# MultiSensorModul_v4.net
KiCad netlist of a schematic drawn in EAGLE
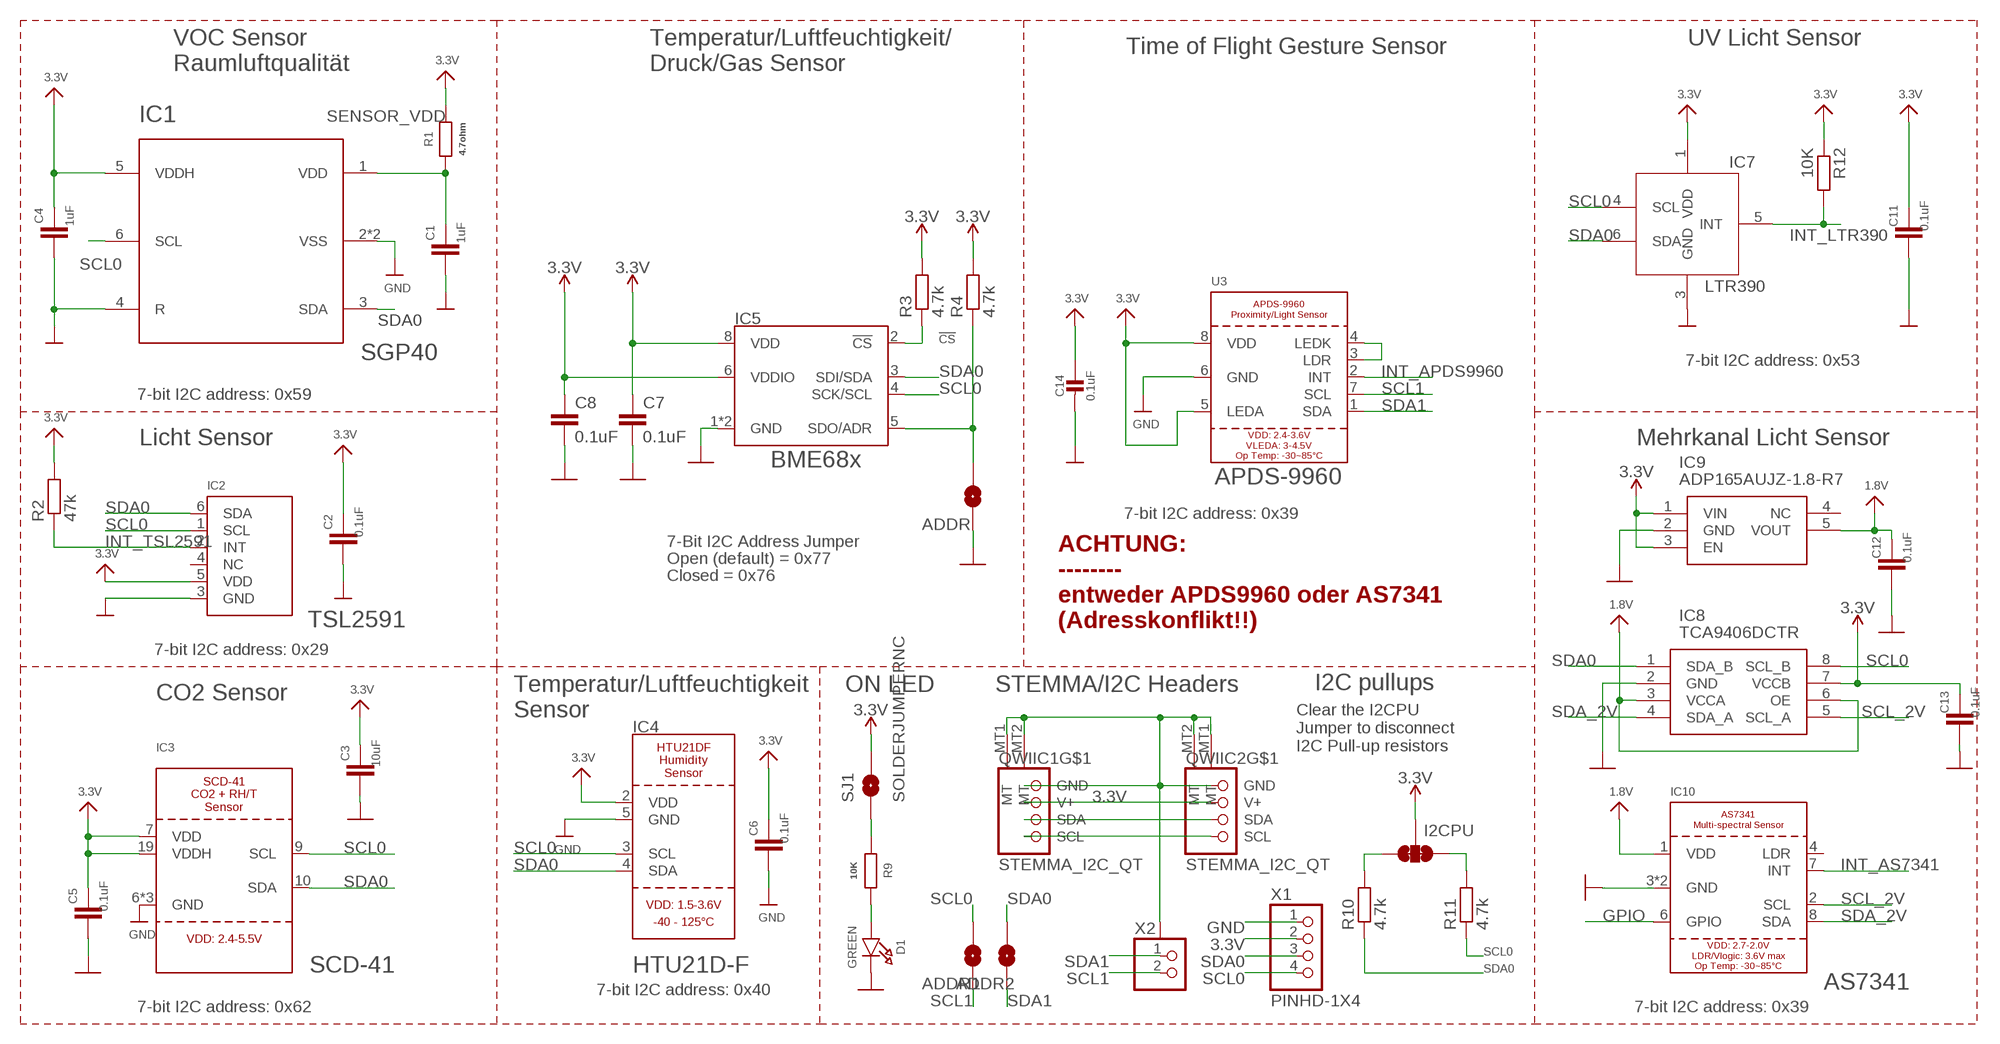
[diagram p0: schematic, sheet 1]

(export (version "E")
  (design (tool "Eeschema 10.0.6"))
  (components
    (comp (ref "ADDR")
      (value "JUMPER-SMT_2_NO_SILK")
      (footprint "eagle-import:SMT-JUMPER_2_NO_SILK")
      (libsource (lib "eagle-import") (part "JUMPER-SMT_2_NO_SILK"))
    )
    (comp (ref "ADDR1")
      (value "JUMPER-SMT_2_NO_SILK")
      (footprint "eagle-import:SMT-JUMPER_2_NO_SILK")
      (libsource (lib "eagle-import") (part "JUMPER-SMT_2_NO_SILK"))
    )
    (comp (ref "ADDR2")
      (value "JUMPER-SMT_2_NO_SILK")
      (footprint "eagle-import:SMT-JUMPER_2_NO_SILK")
      (libsource (lib "eagle-import") (part "JUMPER-SMT_2_NO_SILK"))
    )
    (comp (ref "C1")
      (value "1uF")
      (footprint "eagle-import:C0805")
      (libsource (lib "eagle-import") (part "C-EUC0805"))
    )
    (comp (ref "C2")
      (value "0.1uF")
      (footprint "eagle-import:C0603")
      (libsource (lib "eagle-import") (part "C-EUC0603"))
    )
    (comp (ref "C3")
      (value "10uF")
      (footprint "eagle-import:C0805")
      (libsource (lib "eagle-import") (part "C-EUC0805"))
    )
    (comp (ref "C4")
      (value "1uF")
      (footprint "eagle-import:C0805")
      (libsource (lib "eagle-import") (part "C-EUC0805"))
    )
    (comp (ref "C5")
      (value "0.1uF")
      (footprint "eagle-import:C0603")
      (libsource (lib "eagle-import") (part "C-EUC0603"))
    )
    (comp (ref "C6")
      (value "0.1uF")
      (footprint "eagle-import:C0603")
      (libsource (lib "eagle-import") (part "C-EUC0603"))
    )
    (comp (ref "C7")
      (value "0.1uF")
      (footprint "eagle-import:C0603")
      (libsource (lib "eagle-import") (part "C-EUC0603"))
    )
    (comp (ref "C8")
      (value "0.1uF")
      (footprint "eagle-import:C0603")
      (libsource (lib "eagle-import") (part "C-EUC0603"))
    )
    (comp (ref "C11")
      (value "0.1uF")
      (footprint "eagle-import:C0603")
      (libsource (lib "eagle-import") (part "C-EUC0603"))
    )
    (comp (ref "C12")
      (value "0.1uF")
      (footprint "eagle-import:C0603")
      (libsource (lib "eagle-import") (part "C-EUC0603"))
    )
    (comp (ref "C13")
      (value "0.1uF")
      (footprint "eagle-import:C0603")
      (libsource (lib "eagle-import") (part "C-EUC0603"))
    )
    (comp (ref "C14")
      (value "0.1uF")
      (footprint "eagle-import:0603-NO")
      (libsource (lib "eagle-import") (part "CAP_CERAMIC0603_NO"))
    )
    (comp (ref "D1")
      (value "GREEN")
      (footprint "eagle-import:CHIPLED_0603_NOOUTLINE")
      (libsource (lib "eagle-import") (part "LED0603_NOOUTLINE"))
    )
    (comp (ref "I2CPU")
      (value "I2C PU")
      (footprint "eagle-import:SMT-JUMPER_3_2-NC_TRACE_SILK")
      (libsource (lib "eagle-import") (part "JUMPER-SMT_3_2-NC_TRACE_SILK"))
    )
    (comp (ref "IC1")
      (value "SGP40")
      (footprint "eagle-import:SGP30")
      (libsource (lib "eagle-import") (part "SGP30"))
    )
    (comp (ref "IC2")
      (value "TSL2591")
      (footprint "eagle-import:DFN6_TAOS")
      (libsource (lib "eagle-import") (part "LIGHT_TSL2591"))
    )
    (comp (ref "IC3")
      (value "SCD-41")
      (footprint "eagle-import:SCD41")
      (libsource (lib "eagle-import") (part "SCD-41"))
    )
    (comp (ref "IC4")
      (value "HTU21D-F")
      (footprint "eagle-import:HTU21DF")
      (libsource (lib "eagle-import") (part "HTU21DF"))
    )
    (comp (ref "IC5")
      (value "BME680 Air Quality Sensor")
      (footprint "eagle-import:LGA3.0X3.0")
      (libsource (lib "eagle-import") (part "BME680-LGA"))
    )
    (comp (ref "IC7")
      (value "LTR390")
      (footprint "eagle-import:LTR390")
      (libsource (lib "eagle-import") (part "LTR390"))
    )
    (comp (ref "IC8")
      (value "TCA9406DCTR")
      (footprint "eagle-import:SOP65P400X130-8N")
      (fields (field (name "MOUSER_PART_NUMBER") "595-TCA9406DCTR"))
      (libsource (lib "eagle-import") (part "TCA9406DCTR"))
    )
    (comp (ref "IC9")
      (value "ADP165AUJZ-1.8-R7")
      (footprint "eagle-import:SOT95P280X100-5N")
      (fields
        (field (name "MANUFACTURER_PART_NUMBER") "ADP165AUJZ-3.3-R7")
        (field (name "MOUSER_PART_NUMBER") "584-ADP165AUJZ3.3R7")
      )
      (libsource (lib "eagle-import") (part "ADP165AUJZ-3.3-R7"))
    )
    (comp (ref "IC10")
      (value "AS7341")
      (footprint "eagle-import:AS7341")
      (libsource (lib "eagle-import") (part "AS7341"))
    )
    (comp (ref "QWIIC1")
      (value "STEMMA_I2C_QT")
      (footprint "eagle-import:JST_SH4")
      (libsource (lib "eagle-import") (part "STEMMA_I2C_QT"))
    )
    (comp (ref "QWIIC2")
      (value "STEMMA_I2C_QT")
      (footprint "eagle-import:JST_SH4")
      (libsource (lib "eagle-import") (part "STEMMA_I2C_QT"))
    )
    (comp (ref "R1")
      (value "4.7ohm")
      (footprint "eagle-import:R0603")
      (libsource (lib "eagle-import") (part "R-EU_R0603"))
    )
    (comp (ref "R2")
      (value "47k")
      (footprint "eagle-import:R0603")
      (libsource (lib "eagle-import") (part "R-EU_R0603"))
    )
    (comp (ref "R3")
      (value "4.7k")
      (footprint "eagle-import:R0603")
      (libsource (lib "eagle-import") (part "R-EU_R0603"))
    )
    (comp (ref "R4")
      (value "4.7k")
      (footprint "eagle-import:R0603")
      (libsource (lib "eagle-import") (part "R-EU_R0603"))
    )
    (comp (ref "R9")
      (value "10K")
      (footprint "eagle-import:R0603")
      (libsource (lib "eagle-import") (part "R-EU_R0603"))
    )
    (comp (ref "R10")
      (value "4.7k")
      (footprint "eagle-import:R0603")
      (libsource (lib "eagle-import") (part "R-EU_R0603"))
    )
    (comp (ref "R11")
      (value "4.7k")
      (footprint "eagle-import:R0603")
      (libsource (lib "eagle-import") (part "R-EU_R0603"))
    )
    (comp (ref "R12")
      (value "10K")
      (footprint "eagle-import:R0603")
      (libsource (lib "eagle-import") (part "R-EU_R0603"))
    )
    (comp (ref "SJ1")
      (value "SOLDERJUMPERNC")
      (footprint "eagle-import:SJ_2S")
      (libsource (lib "eagle-import") (part "SOLDERJUMPERNC"))
    )
    (comp (ref "U3")
      (value "APDS-9960")
      (footprint "eagle-import:APDS-9960")
      (libsource (lib "eagle-import") (part "APDS-9960"))
    )
    (comp (ref "X1")
      (value "PINHD-1X4")
      (footprint "eagle-import:1X04")
      (libsource (lib "eagle-import") (part "PINHD-1X4"))
    )
    (comp (ref "X2")
      (value "PINHD-1X2")
      (footprint "eagle-import:1X02")
      (libsource (lib "eagle-import") (part "PINHD-1X2"))
    )
  )
  (nets
    (net (code "1") (name "/GPIO") (class "Default")
      (node (ref "IC10") (pin "6") (pinfunction "GPIO_6") (pintype "power_in"))
    )
    (net (code "2") (name "/INT_APDS9960") (class "Default")
      (node (ref "U3") (pin "2") (pinfunction "INT_2") (pintype "output"))
    )
    (net (code "3") (name "/INT_AS7341") (class "Default")
      (node (ref "IC10") (pin "7") (pinfunction "INT_7") (pintype "output"))
    )
    (net (code "4") (name "/INT_LTR390") (class "Default")
      (node (ref "IC7") (pin "5") (pinfunction "INT_5") (pintype "bidirectional"))
      (node (ref "R12") (pin "2") (pinfunction "2_2") (pintype "passive"))
    )
    (net (code "5") (name "/INT_TSL2591") (class "Default")
      (node (ref "IC2") (pin "2") (pinfunction "INT_2") (pintype "output"))
      (node (ref "R2") (pin "1") (pinfunction "1_1") (pintype "passive"))
    )
    (net (code "6") (name "/SCL1") (class "Default")
      (node (ref "ADDR1") (pin "1") (pinfunction "1_1") (pintype "passive"))
      (node (ref "U3") (pin "7") (pinfunction "SCL_7") (pintype "input"))
      (node (ref "X2") (pin "2") (pinfunction "2_2") (pintype "passive"))
    )
    (net (code "7") (name "/SCL_2V") (class "Default")
      (node (ref "IC10") (pin "2") (pinfunction "SCL_2") (pintype "input"))
      (node (ref "IC8") (pin "5") (pinfunction "SCL_A_5") (pintype "bidirectional"))
    )
    (net (code "8") (name "/SDA1") (class "Default")
      (node (ref "ADDR2") (pin "1") (pinfunction "1_1") (pintype "passive"))
      (node (ref "U3") (pin "1") (pinfunction "SDA_1") (pintype "bidirectional"))
      (node (ref "X2") (pin "1") (pinfunction "1_1") (pintype "passive"))
    )
    (net (code "9") (name "/SDA_2V") (class "Default")
      (node (ref "IC10") (pin "8") (pinfunction "SDA_8") (pintype "bidirectional"))
      (node (ref "IC8") (pin "4") (pinfunction "SDA_A_4") (pintype "bidirectional"))
    )
    (net (code "10") (name "/SENSOR_VDD") (class "Default")
      (node (ref "C1") (pin "1") (pinfunction "1_1") (pintype "passive"))
      (node (ref "IC1") (pin "1") (pinfunction "VDD_1") (pintype "bidirectional"))
      (node (ref "R1") (pin "1") (pinfunction "1_1") (pintype "passive"))
    )
    (net (code "11") (name "/~{CS}") (class "Default")
      (node (ref "IC5") (pin "2") (pinfunction "~{CS}_2") (pintype "bidirectional"))
      (node (ref "R3") (pin "1") (pinfunction "1_1") (pintype "passive"))
    )
    (net (code "12") (name "1.8V") (class "Default")
      (node (ref "C12") (pin "1") (pinfunction "1_1") (pintype "passive"))
      (node (ref "IC10") (pin "1") (pinfunction "VDD_1") (pintype "power_in"))
      (node (ref "IC8") (pin "3") (pinfunction "VCCA_3") (pintype "bidirectional"))
      (node (ref "IC8") (pin "6") (pinfunction "OE_6") (pintype "bidirectional"))
      (node (ref "IC9") (pin "5") (pinfunction "VOUT_5") (pintype "bidirectional"))
    )
    (net (code "13") (name "3.3V") (class "Default")
      (node (ref "C11") (pin "1") (pinfunction "1_1") (pintype "passive"))
      (node (ref "C13") (pin "1") (pinfunction "1_1") (pintype "passive"))
      (node (ref "C14") (pin "1") (pinfunction "1_1") (pintype "passive"))
      (node (ref "C2") (pin "1") (pinfunction "1_1") (pintype "passive"))
      (node (ref "C3") (pin "1") (pinfunction "1_1") (pintype "passive"))
      (node (ref "C4") (pin "1") (pinfunction "1_1") (pintype "passive"))
      (node (ref "C5") (pin "1") (pinfunction "1_1") (pintype "passive"))
      (node (ref "C6") (pin "1") (pinfunction "1_1") (pintype "passive"))
      (node (ref "C7") (pin "1") (pinfunction "1_1") (pintype "passive"))
      (node (ref "C8") (pin "1") (pinfunction "1_1") (pintype "passive"))
      (node (ref "I2CPU") (pin "2") (pinfunction "2_2") (pintype "passive"))
      (node (ref "IC1") (pin "5") (pinfunction "VDDH_5") (pintype "bidirectional"))
      (node (ref "IC2") (pin "5") (pinfunction "VDD_5") (pintype "power_in"))
      (node (ref "IC3") (pin "19") (pinfunction "VDDH_19") (pintype "power_in"))
      (node (ref "IC3") (pin "7") (pinfunction "VDD_7") (pintype "power_in"))
      (node (ref "IC4") (pin "2") (pinfunction "VDD_2") (pintype "power_in"))
      (node (ref "IC5") (pin "6") (pinfunction "VDDIO_6") (pintype "bidirectional"))
      (node (ref "IC5") (pin "8") (pinfunction "VDD_8") (pintype "bidirectional"))
      (node (ref "IC7") (pin "1") (pinfunction "VDD_1") (pintype "power_in"))
      (node (ref "IC8") (pin "7") (pinfunction "VCCB_7") (pintype "bidirectional"))
      (node (ref "IC9") (pin "1") (pinfunction "VIN_1") (pintype "bidirectional"))
      (node (ref "IC9") (pin "3") (pinfunction "EN_3") (pintype "bidirectional"))
      (node (ref "QWIIC1") (pin "2") (pinfunction "V+_2") (pintype "passive"))
      (node (ref "QWIIC2") (pin "2") (pinfunction "V+_2") (pintype "passive"))
      (node (ref "R1") (pin "2") (pinfunction "2_2") (pintype "passive"))
      (node (ref "R12") (pin "1") (pinfunction "1_1") (pintype "passive"))
      (node (ref "R2") (pin "2") (pinfunction "2_2") (pintype "passive"))
      (node (ref "R3") (pin "2") (pinfunction "2_2") (pintype "passive"))
      (node (ref "R4") (pin "2") (pinfunction "2_2") (pintype "passive"))
      (node (ref "SJ1") (pin "2") (pinfunction "2_2") (pintype "passive"))
      (node (ref "U3") (pin "5") (pinfunction "LEDA_5") (pintype "power_in"))
      (node (ref "U3") (pin "8") (pinfunction "VDD_8") (pintype "power_in"))
      (node (ref "X1") (pin "2") (pinfunction "2_2") (pintype "passive"))
    )
    (net (code "14") (name "GND") (class "Default")
      (node (ref "ADDR") (pin "1") (pinfunction "1_1") (pintype "passive"))
      (node (ref "C1") (pin "2") (pinfunction "2_2") (pintype "passive"))
      (node (ref "C11") (pin "2") (pinfunction "2_2") (pintype "passive"))
      (node (ref "C12") (pin "2") (pinfunction "2_2") (pintype "passive"))
      (node (ref "C13") (pin "2") (pinfunction "2_2") (pintype "passive"))
      (node (ref "C14") (pin "2") (pinfunction "2_2") (pintype "passive"))
      (node (ref "C2") (pin "2") (pinfunction "2_2") (pintype "passive"))
      (node (ref "C3") (pin "2") (pinfunction "2_2") (pintype "passive"))
      (node (ref "C4") (pin "2") (pinfunction "2_2") (pintype "passive"))
      (node (ref "C5") (pin "2") (pinfunction "2_2") (pintype "passive"))
      (node (ref "C6") (pin "2") (pinfunction "2_2") (pintype "passive"))
      (node (ref "C7") (pin "2") (pinfunction "2_2") (pintype "passive"))
      (node (ref "C8") (pin "2") (pinfunction "2_2") (pintype "passive"))
      (node (ref "D1") (pin "C") (pinfunction "C_C") (pintype "passive"))
      (node (ref "IC1") (pin "2") (pinfunction "VSS_2") (pintype "bidirectional"))
      (node (ref "IC1") (pin "4") (pinfunction "R_4") (pintype "bidirectional"))
      (node (ref "IC1") (pin "P$7") (pinfunction "VSS_P$7") (pintype "bidirectional"))
      (node (ref "IC10") (pin "3") (pinfunction "GND_3") (pintype "power_in"))
      (node (ref "IC10") (pin "5") (pinfunction "GND_5") (pintype "power_in"))
      (node (ref "IC2") (pin "3") (pinfunction "GND_3") (pintype "power_in"))
      (node (ref "IC3") (pin "20") (pinfunction "GND_20") (pintype "power_in"))
      (node (ref "IC3") (pin "6") (pinfunction "GND_6") (pintype "power_in"))
      (node (ref "IC3") (pin "P$1") (pinfunction "GND_P$1") (pintype "power_in"))
      (node (ref "IC4") (pin "5") (pinfunction "GND_5") (pintype "power_in"))
      (node (ref "IC5") (pin "1") (pinfunction "GND_1") (pintype "bidirectional"))
      (node (ref "IC5") (pin "7") (pinfunction "GND_7") (pintype "bidirectional"))
      (node (ref "IC7") (pin "3") (pinfunction "GND_3") (pintype "power_in"))
      (node (ref "IC8") (pin "2") (pinfunction "GND_2") (pintype "bidirectional"))
      (node (ref "IC9") (pin "2") (pinfunction "GND_2") (pintype "bidirectional"))
      (node (ref "QWIIC1") (pin "1") (pinfunction "GND_1") (pintype "passive"))
      (node (ref "QWIIC1") (pin "MT1") (pinfunction "MT_MT1") (pintype "bidirectional"))
      (node (ref "QWIIC1") (pin "MT2") (pinfunction "MT_MT2") (pintype "bidirectional"))
      (node (ref "QWIIC2") (pin "1") (pinfunction "GND_1") (pintype "passive"))
      (node (ref "QWIIC2") (pin "MT1") (pinfunction "MT_MT1") (pintype "bidirectional"))
      (node (ref "QWIIC2") (pin "MT2") (pinfunction "MT_MT2") (pintype "bidirectional"))
      (node (ref "U3") (pin "6") (pinfunction "GND_6") (pintype "power_in"))
      (node (ref "X1") (pin "1") (pinfunction "1_1") (pintype "passive"))
    )
    (net (code "15") (name "Net-(D1-PadA)") (class "Default")
      (node (ref "D1") (pin "A") (pinfunction "A_A") (pintype "passive"))
      (node (ref "R9") (pin "2") (pinfunction "2_2") (pintype "passive"))
    )
    (net (code "16") (name "Net-(I2CPU-Pad1)") (class "Default")
      (node (ref "I2CPU") (pin "1") (pinfunction "1_1") (pintype "passive"))
      (node (ref "R11") (pin "2") (pinfunction "2_2") (pintype "passive"))
    )
    (net (code "17") (name "Net-(I2CPU-Pad3)") (class "Default")
      (node (ref "I2CPU") (pin "3") (pinfunction "3_3") (pintype "passive"))
      (node (ref "R10") (pin "2") (pinfunction "2_2") (pintype "passive"))
    )
    (net (code "18") (name "Net-(IC5-SDO{slash}ADR)") (class "Default")
      (node (ref "ADDR") (pin "2") (pinfunction "2_2") (pintype "passive"))
      (node (ref "IC5") (pin "5") (pinfunction "SDO/ADR_5") (pintype "bidirectional"))
      (node (ref "R4") (pin "1") (pinfunction "1_1") (pintype "passive"))
    )
    (net (code "19") (name "Net-(R9-Pad1)") (class "Default")
      (node (ref "R9") (pin "1") (pinfunction "1_1") (pintype "passive"))
      (node (ref "SJ1") (pin "1") (pinfunction "1_1") (pintype "passive"))
    )
    (net (code "20") (name "Net-(U3-LDR)") (class "Default")
      (node (ref "U3") (pin "3") (pinfunction "LDR_3") (pintype "bidirectional"))
      (node (ref "U3") (pin "4") (pinfunction "LEDK_4") (pintype "bidirectional"))
    )
    (net (code "21") (name "SCL0") (class "Default")
      (node (ref "ADDR1") (pin "2") (pinfunction "2_2") (pintype "passive"))
      (node (ref "IC1") (pin "6") (pinfunction "SCL_6") (pintype "bidirectional"))
      (node (ref "IC2") (pin "1") (pinfunction "SCL_1") (pintype "bidirectional"))
      (node (ref "IC3") (pin "9") (pinfunction "SCL_9") (pintype "input"))
      (node (ref "IC4") (pin "3") (pinfunction "SCL_3") (pintype "input"))
      (node (ref "IC5") (pin "4") (pinfunction "SCK/SCL_4") (pintype "bidirectional"))
      (node (ref "IC7") (pin "4") (pinfunction "SCL_4") (pintype "bidirectional"))
      (node (ref "IC8") (pin "8") (pinfunction "SCL_B_8") (pintype "bidirectional"))
      (node (ref "QWIIC1") (pin "4") (pinfunction "SCL_4") (pintype "passive"))
      (node (ref "QWIIC2") (pin "4") (pinfunction "SCL_4") (pintype "passive"))
      (node (ref "R11") (pin "1") (pinfunction "1_1") (pintype "passive"))
      (node (ref "X1") (pin "4") (pinfunction "4_4") (pintype "passive"))
    )
    (net (code "22") (name "SDA0") (class "Default")
      (node (ref "ADDR2") (pin "2") (pinfunction "2_2") (pintype "passive"))
      (node (ref "IC1") (pin "3") (pinfunction "SDA_3") (pintype "bidirectional"))
      (node (ref "IC2") (pin "6") (pinfunction "SDA_6") (pintype "bidirectional"))
      (node (ref "IC3") (pin "10") (pinfunction "SDA_10") (pintype "bidirectional"))
      (node (ref "IC4") (pin "4") (pinfunction "SDA_4") (pintype "bidirectional"))
      (node (ref "IC5") (pin "3") (pinfunction "SDI/SDA_3") (pintype "bidirectional"))
      (node (ref "IC7") (pin "6") (pinfunction "SDA_6") (pintype "bidirectional"))
      (node (ref "IC8") (pin "1") (pinfunction "SDA_B_1") (pintype "bidirectional"))
      (node (ref "QWIIC1") (pin "3") (pinfunction "SDA_3") (pintype "passive"))
      (node (ref "QWIIC2") (pin "3") (pinfunction "SDA_3") (pintype "passive"))
      (node (ref "R10") (pin "1") (pinfunction "1_1") (pintype "passive"))
      (node (ref "X1") (pin "3") (pinfunction "3_3") (pintype "passive"))
    )
    (net (code "23") (name "unconnected-(IC2-NC-Pad4)") (class "Default")
      (node (ref "IC2") (pin "4") (pinfunction "NC_4") (pintype "no_connect"))
    )
    (net (code "24") (name "unconnected-(IC9-NC-Pad4)") (class "Default")
      (node (ref "IC9") (pin "4") (pinfunction "NC_4") (pintype "no_connect"))
    )
    (net (code "25") (name "unconnected-(IC10-LDR-Pad4)") (class "Default")
      (node (ref "IC10") (pin "4") (pinfunction "LDR_4") (pintype "bidirectional"))
    )
  )
)
